# STM32F103T8.net
KiCad netlist of a schematic drawn in Altium Designer
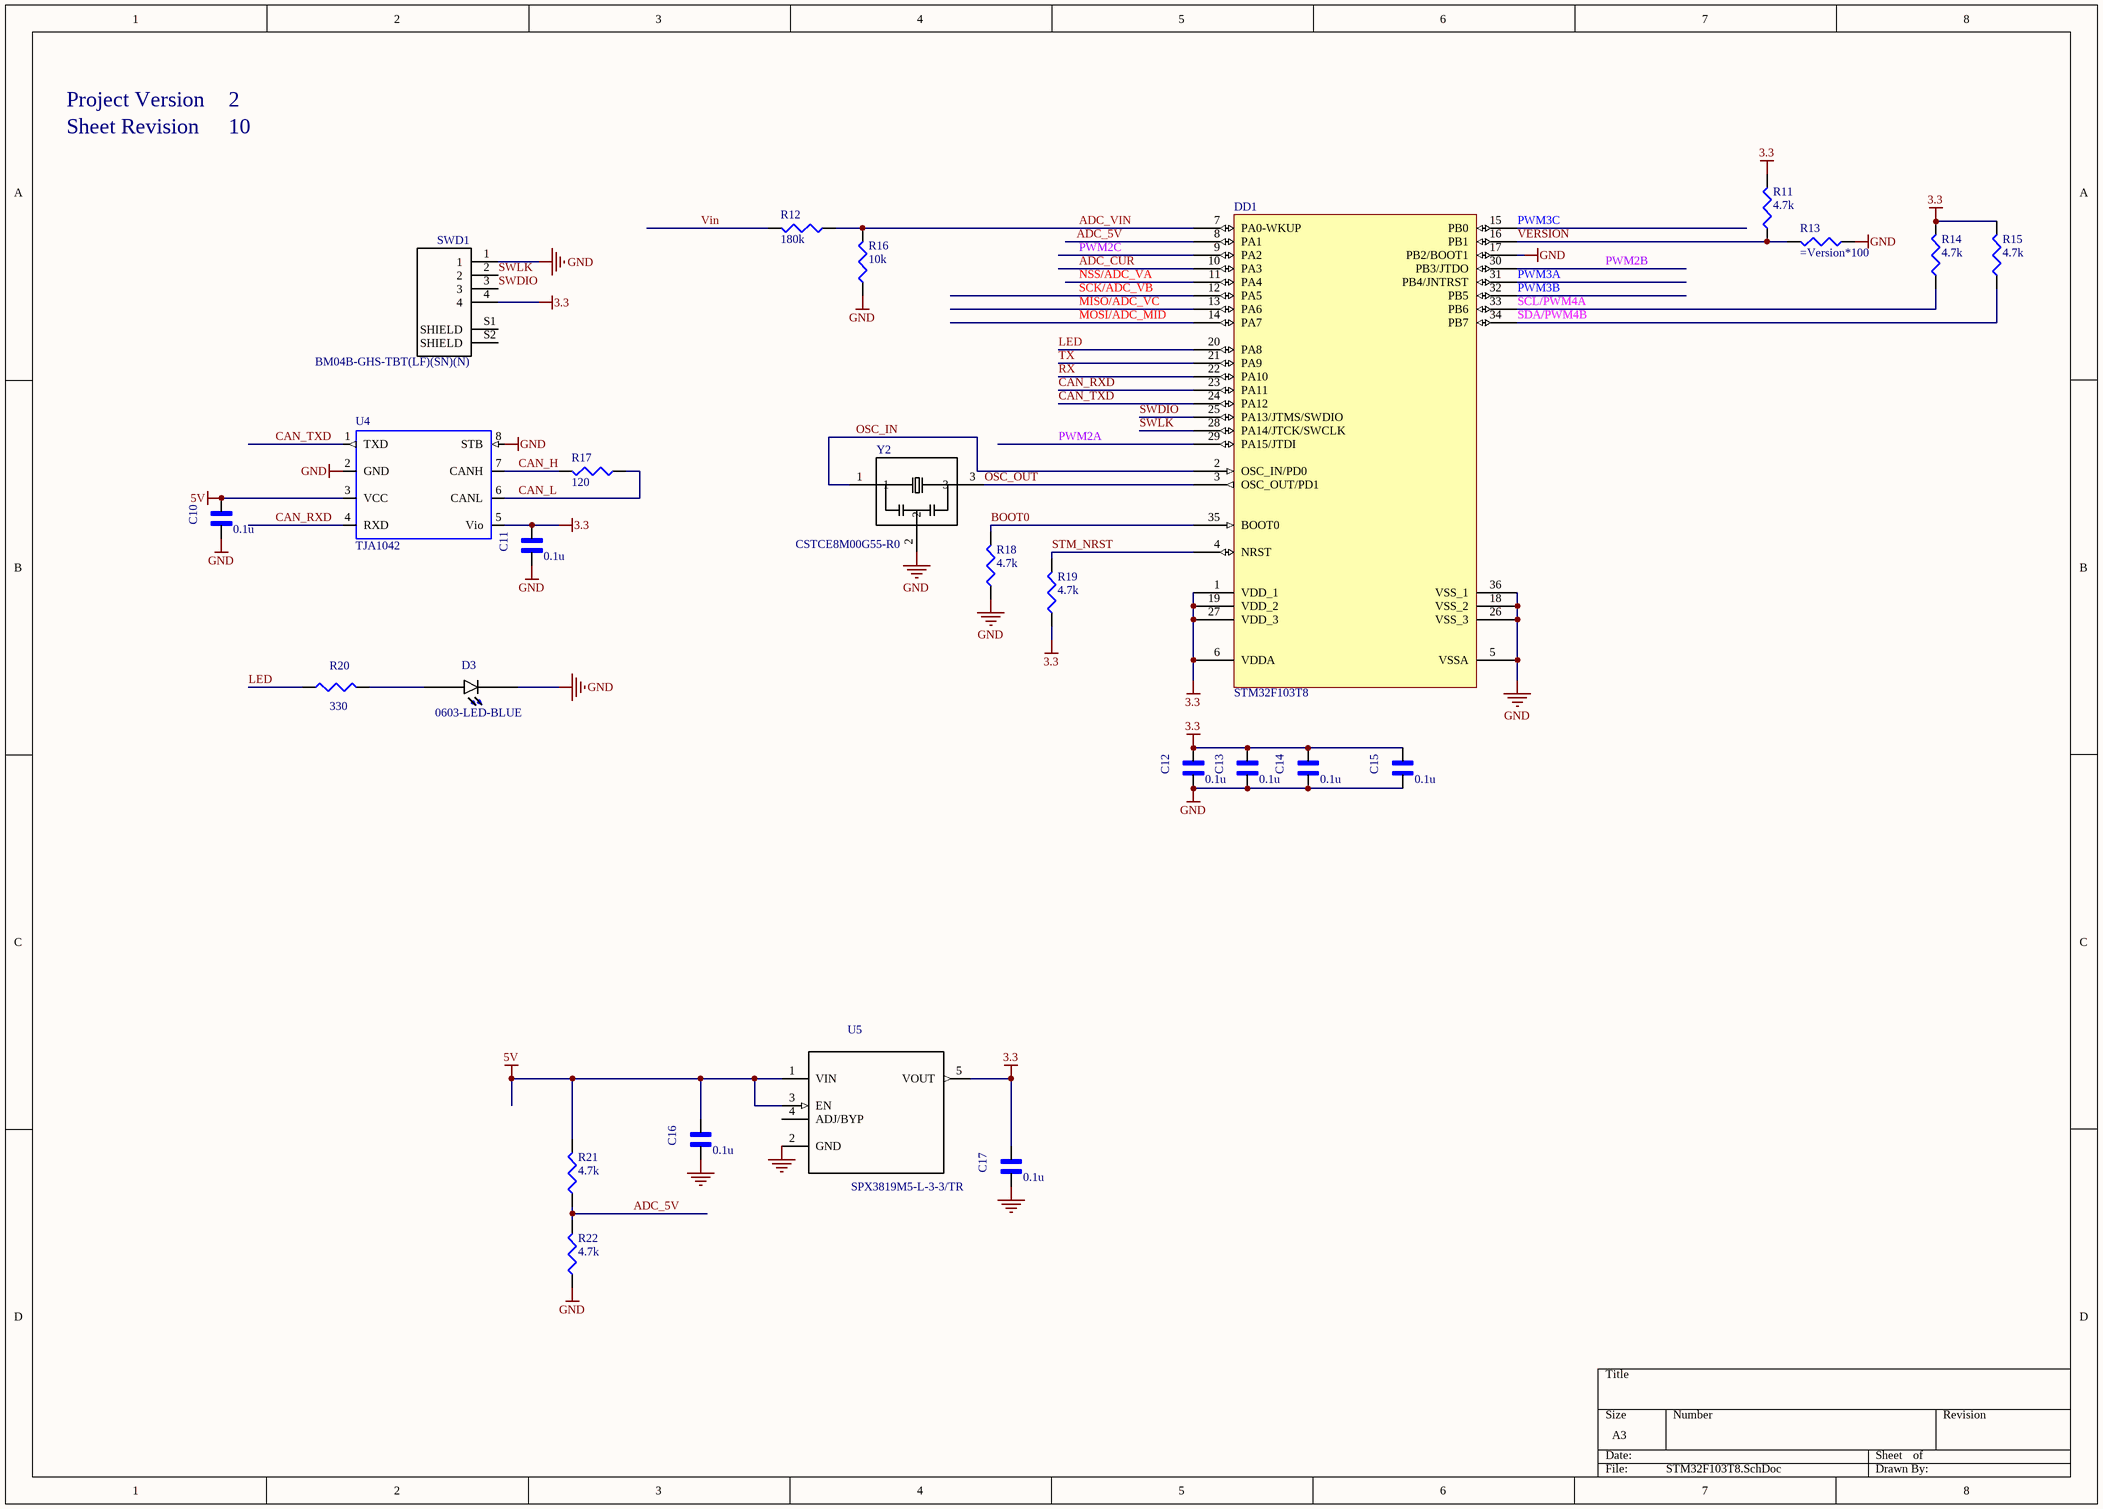
[diagram p0: STM32F103T8.SchDoc]

(export (version "E")
  (design (tool "Eeschema 10.0.6"))
  (components
    (comp (ref "C10")
      (value "0.1u")
      (footprint "*CAPC1608X90")
      (description "Cap Thin Film 0.1uf 50v 0603")
      (fields (field (name "MF") "AVX") (field (name "MP") "GX035C104MAT2-500"))
      (libsource (lib "lib") (part "GX035C104MAT2-500"))
    )
    (comp (ref "C11")
      (value "0.1u")
      (footprint "*CAPC1608X90")
      (description "Cap Thin Film 0.1uf 50v 0603")
      (fields (field (name "MF") "AVX") (field (name "MP") "GX035C104MAT2-500"))
      (libsource (lib "lib") (part "GX035C104MAT2-500"))
    )
    (comp (ref "C12")
      (value "0.1u")
      (footprint "*CAPC1608X90")
      (description "Cap Thin Film 0.1uf 50v 0603")
      (fields (field (name "MF") "AVX") (field (name "MP") "GX035C104MAT2-500"))
      (libsource (lib "lib") (part "GX035C104MAT2-500"))
    )
    (comp (ref "C13")
      (value "0.1u")
      (footprint "*CAPC1608X90")
      (description "Cap Thin Film 0.1uf 50v 0603")
      (fields (field (name "MF") "AVX") (field (name "MP") "GX035C104MAT2-500"))
      (libsource (lib "lib") (part "GX035C104MAT2-500"))
    )
    (comp (ref "C14")
      (value "0.1u")
      (footprint "*CAPC1608X90")
      (description "Cap Thin Film 0.1uf 50v 0603")
      (fields (field (name "MF") "AVX") (field (name "MP") "GX035C104MAT2-500"))
      (libsource (lib "lib") (part "GX035C104MAT2-500"))
    )
    (comp (ref "C15")
      (value "0.1u")
      (footprint "*CAPC1608X90")
      (description "Cap Thin Film 0.1uf 50v 0603")
      (fields (field (name "MF") "AVX") (field (name "MP") "GX035C104MAT2-500"))
      (libsource (lib "lib") (part "GX035C104MAT2-500"))
    )
    (comp (ref "C16")
      (value "0.1u")
      (footprint "*CAPC1608X90")
      (description "Cap Thin Film 0.1uf 50v 0603")
      (fields (field (name "MF") "AVX") (field (name "MP") "GX035C104MAT2-500"))
      (libsource (lib "lib") (part "GX035C104MAT2-500"))
    )
    (comp (ref "C17")
      (value "0.1u")
      (footprint "*CAPC1608X90")
      (description "Cap Thin Film 0.1uf 50v 0603")
      (fields (field (name "MF") "AVX") (field (name "MP") "GX035C104MAT2-500"))
      (libsource (lib "lib") (part "GX035C104MAT2-500"))
    )
    (comp (ref "D3")
      (value "0603-LED-BLUE")
      (footprint "*LEDM1608X80_LTE-C1906R-14(Primary)")
      (description "LED IrLED Chip LED 2-Pin SMD T/R")
      (libsource (lib "lib") (part "LTE-C1906R-14"))
    )
    (comp (ref "DD1")
      (value "STM32F103T8")
      (footprint "*QFN50P600X600X100-37N")
      (description "STM32F103T8U6, Микроконтроллер 32BIT ARM 64K FLASH [VFQFPN-36]")
      (fields (field (name "MF") "STM") (field (name "MP") "STM32F103T8U6"))
      (libsource (lib "lib") (part "STM32F103T8"))
    )
    (comp (ref "R11")
      (value "4.7k")
      (footprint "J1-0603")
      (description "Resistor")
      (fields (field (name "MP") "4.7K 1% 0603") (field (name "Comment") "Res3"))
      (libsource (lib "Miscellaneous Devices") (part "Res3"))
    )
    (comp (ref "R12")
      (value "180k")
      (footprint "J1-0603")
      (description "Resistor")
      (fields (field (name "MP") "180K 1% 0603") (field (name "Comment") "Res3"))
      (libsource (lib "Miscellaneous Devices") (part "Res3"))
    )
    (comp (ref "R13")
      (value "Res3")
      (footprint "J1-0603")
      (description "Resistor")
      (fields (field (name "MP") "4.7K 1% 0603"))
      (libsource (lib "Miscellaneous Devices") (part "Res3"))
    )
    (comp (ref "R14")
      (value "4.7k")
      (footprint "J1-0603")
      (description "Resistor")
      (fields (field (name "MP") "4.7K 1% 0603") (field (name "Comment") "Res3"))
      (libsource (lib "Miscellaneous Devices") (part "Res3"))
    )
    (comp (ref "R15")
      (value "4.7k")
      (footprint "J1-0603")
      (description "Resistor")
      (fields (field (name "MP") "4.7K 1% 0603") (field (name "Comment") "Res3"))
      (libsource (lib "Miscellaneous Devices") (part "Res3"))
    )
    (comp (ref "R16")
      (value "10k")
      (footprint "J1-0603")
      (description "Resistor")
      (fields (field (name "MP") "4.7K 1% 0603") (field (name "Comment") "Res3"))
      (libsource (lib "Miscellaneous Devices") (part "Res3"))
    )
    (comp (ref "R17")
      (value "120")
      (footprint "J1-0603")
      (description "120 Ohms 1 0.1 W 1 10 W Chip Resistor 0603 1608 Metric Thick Film")
      (fields (field (name "MP") "RC0603FR-07120RL") (field (name "Comment") "Res3"))
      (libsource (lib "Miscellaneous Devices") (part "Res3"))
    )
    (comp (ref "R18")
      (value "4.7k")
      (footprint "J1-0603")
      (description "Resistor")
      (fields (field (name "MP") "4.7K 1% 0603") (field (name "Comment") "Res3"))
      (libsource (lib "Miscellaneous Devices") (part "Res3"))
    )
    (comp (ref "R19")
      (value "4.7k")
      (footprint "J1-0603")
      (description "Resistor")
      (fields (field (name "MP") "4.7K 1% 0603") (field (name "Comment") "Res3"))
      (libsource (lib "Miscellaneous Devices") (part "Res3"))
    )
    (comp (ref "R20")
      (value "330")
      (footprint "J1-0603")
      (description "Resistor")
      (fields (field (name "MP") "RC0603FR-07330RL") (field (name "Comment") "Res3"))
      (libsource (lib "Miscellaneous Devices") (part "Res3"))
    )
    (comp (ref "R21")
      (value "4.7k")
      (footprint "J1-0603")
      (description "Resistor")
      (fields (field (name "MP") "4.7K 1% 0603") (field (name "Comment") "Res3"))
      (libsource (lib "Miscellaneous Devices") (part "Res3"))
    )
    (comp (ref "R22")
      (value "4.7k")
      (footprint "J1-0603")
      (description "Resistor")
      (fields (field (name "MP") "4.7K 1% 0603") (field (name "Comment") "Res3"))
      (libsource (lib "Miscellaneous Devices") (part "Res3"))
    )
    (comp (ref "SWD1")
      (value "BM04B-GHS-TBT(LF)(SN)(N)")
      (footprint "JST_BM04B-GHS-holes")
      (description "Conn Shrouded Header HDR 4 POS 1.25mm Solder ST SMD Reel")
      (fields (field (name "MF") "JST Sales") (field (name "MP") "SM04B-GHS-TB(LF)(SN)"))
      (libsource (lib "lib") (part "BM04B-GHS-TBT(LF)(SN)(N)"))
    )
    (comp (ref "U4")
      (value "TJA1042")
      (footprint "SOT782-1")
      (description "1/1 Transceiver Half CANbus 8-SO")
      (fields (field (name "MF") "NXP USA"))
      (libsource (lib "lib") (part "TJA1042"))
    )
    (comp (ref "U5")
      (value "SPX3819M5-L-3-3/TR")
      (footprint "*SOT95P280X145-5N")
      (description "Low Dropout Voltage Regulator, Adjustable 0.5A, В±1%, 2.5 to 16 Vin, 5-Pin SOT-23")
      (fields (field (name "MF") "MaxLinear, Inc."))
      (libsource (lib "DC_DC") (part "SPX3819M5-L"))
    )
    (comp (ref "Y2")
      (value "CSTCE8M00G55-R0")
      (footprint "*OSC_CSTCE8M00G55-R0")
      (description "Ceramic Resonator 8MHz ??0.5% _Tol_ ??0.2% _Stability_ 33pF 40Ohm 3-Pin CSMD T/R")
      (fields (field (name "MF") "Murata"))
      (libsource (lib "DC_DC") (part "CSTCE8M00G55-R0"))
    )
  )
  (nets
    (net (code "1") (name "/ADC_5V") (class "Default")
      (node (ref "DD1") (pin "8") (pinfunction "PA1_8") (pintype "bidirectional"))
      (node (ref "R21") (pin "1") (pinfunction "1_1") (pintype "passive"))
      (node (ref "R22") (pin "2") (pinfunction "2_2") (pintype "passive"))
    )
    (net (code "2") (name "/ADC_CUR") (class "Default")
      (node (ref "DD1") (pin "10") (pinfunction "PA3_10") (pintype "bidirectional"))
    )
    (net (code "3") (name "/ADC_VIN") (class "Default")
      (node (ref "DD1") (pin "7") (pinfunction "PA0-WKUP_7") (pintype "bidirectional"))
      (node (ref "R12") (pin "1") (pinfunction "1_1") (pintype "passive"))
      (node (ref "R16") (pin "2") (pinfunction "2_2") (pintype "passive"))
    )
    (net (code "4") (name "/BOOT0") (class "Default")
      (node (ref "DD1") (pin "35") (pinfunction "BOOT0_35") (pintype "input"))
      (node (ref "R18") (pin "2") (pinfunction "2_2") (pintype "passive"))
    )
    (net (code "5") (name "/CAN_H") (class "Default")
      (node (ref "R17") (pin "2") (pinfunction "2_2") (pintype "passive"))
      (node (ref "U4") (pin "7") (pinfunction "CANH_7") (pintype "bidirectional"))
    )
    (net (code "6") (name "/CAN_L") (class "Default")
      (node (ref "R17") (pin "1") (pinfunction "1_1") (pintype "passive"))
      (node (ref "U4") (pin "6") (pinfunction "CANL_6") (pintype "bidirectional"))
    )
    (net (code "7") (name "/CAN_RXD") (class "Default")
      (node (ref "DD1") (pin "23") (pinfunction "PA11_23") (pintype "bidirectional"))
      (node (ref "U4") (pin "4") (pinfunction "RXD_4") (pintype "bidirectional"))
    )
    (net (code "8") (name "/CAN_TXD") (class "Default")
      (node (ref "DD1") (pin "24") (pinfunction "PA12_24") (pintype "bidirectional"))
      (node (ref "U4") (pin "1") (pinfunction "TXD_1") (pintype "output"))
    )
    (net (code "9") (name "/LED") (class "Default")
      (node (ref "DD1") (pin "20") (pinfunction "PA8_20") (pintype "bidirectional"))
      (node (ref "R20") (pin "1") (pinfunction "1_1") (pintype "passive"))
    )
    (net (code "10") (name "/MISO{slash}ADC_VC") (class "Default")
      (node (ref "DD1") (pin "13") (pinfunction "PA6_13") (pintype "bidirectional"))
    )
    (net (code "11") (name "/MOSI{slash}ADC_MID") (class "Default")
      (node (ref "DD1") (pin "14") (pinfunction "PA7_14") (pintype "bidirectional"))
    )
    (net (code "12") (name "/NSS{slash}ADC_VA") (class "Default")
      (node (ref "DD1") (pin "11") (pinfunction "PA4_11") (pintype "bidirectional"))
    )
    (net (code "13") (name "/OSC_IN") (class "Default")
      (node (ref "DD1") (pin "2") (pinfunction "OSC_IN/PD0_2") (pintype "input"))
      (node (ref "Y2") (pin "1") (pinfunction "1_1") (pintype "passive"))
    )
    (net (code "14") (name "/OSC_OUT") (class "Default")
      (node (ref "DD1") (pin "3") (pinfunction "OSC_OUT/PD1_3") (pintype "output"))
      (node (ref "Y2") (pin "3") (pinfunction "3_3") (pintype "passive"))
    )
    (net (code "15") (name "/PWM2A") (class "Default")
      (node (ref "DD1") (pin "29") (pinfunction "PA15/JTDI_29") (pintype "bidirectional"))
    )
    (net (code "16") (name "/PWM2B") (class "Default")
      (node (ref "DD1") (pin "30") (pinfunction "PB3/JTDO_30") (pintype "bidirectional"))
    )
    (net (code "17") (name "/PWM2C") (class "Default")
      (node (ref "DD1") (pin "9") (pinfunction "PA2_9") (pintype "bidirectional"))
    )
    (net (code "18") (name "/PWM3A") (class "Default")
      (node (ref "DD1") (pin "31") (pinfunction "PB4/JNTRST_31") (pintype "bidirectional"))
    )
    (net (code "19") (name "/PWM3B") (class "Default")
      (node (ref "DD1") (pin "32") (pinfunction "PB5_32") (pintype "bidirectional"))
    )
    (net (code "20") (name "/PWM3C") (class "Default")
      (node (ref "DD1") (pin "15") (pinfunction "PB0_15") (pintype "bidirectional"))
    )
    (net (code "21") (name "/RX") (class "Default")
      (node (ref "DD1") (pin "22") (pinfunction "PA10_22") (pintype "bidirectional"))
    )
    (net (code "22") (name "/SCK{slash}ADC_VB") (class "Default")
      (node (ref "DD1") (pin "12") (pinfunction "PA5_12") (pintype "bidirectional"))
    )
    (net (code "23") (name "/SCL{slash}PWM4A") (class "Default")
      (node (ref "DD1") (pin "33") (pinfunction "PB6_33") (pintype "bidirectional"))
      (node (ref "R14") (pin "1") (pinfunction "1_1") (pintype "passive"))
    )
    (net (code "24") (name "/SDA{slash}PWM4B") (class "Default")
      (node (ref "DD1") (pin "34") (pinfunction "PB7_34") (pintype "bidirectional"))
      (node (ref "R15") (pin "1") (pinfunction "1_1") (pintype "passive"))
    )
    (net (code "25") (name "/STM_NRST") (class "Default")
      (node (ref "DD1") (pin "4") (pinfunction "NRST_4") (pintype "bidirectional"))
      (node (ref "R19") (pin "2") (pinfunction "2_2") (pintype "passive"))
    )
    (net (code "26") (name "/SWDIO") (class "Default")
      (node (ref "DD1") (pin "25") (pinfunction "PA13/JTMS/SWDIO_25") (pintype "bidirectional"))
      (node (ref "SWD1") (pin "3") (pinfunction "3_3") (pintype "passive"))
    )
    (net (code "27") (name "/SWLK") (class "Default")
      (node (ref "DD1") (pin "28") (pinfunction "PA14/JTCK/SWCLK_28") (pintype "bidirectional"))
      (node (ref "SWD1") (pin "2") (pinfunction "2_2") (pintype "passive"))
    )
    (net (code "28") (name "/TX") (class "Default")
      (node (ref "DD1") (pin "21") (pinfunction "PA9_21") (pintype "bidirectional"))
    )
    (net (code "29") (name "/VERSION") (class "Default")
      (node (ref "DD1") (pin "16") (pinfunction "PB1_16") (pintype "bidirectional"))
      (node (ref "R11") (pin "1") (pinfunction "1_1") (pintype "passive"))
      (node (ref "R13") (pin "2") (pinfunction "2_2") (pintype "passive"))
    )
    (net (code "30") (name "/Vin") (class "Default")
      (node (ref "R12") (pin "2") (pinfunction "2_2") (pintype "passive"))
    )
    (net (code "31") (name "3.3") (class "Default")
      (node (ref "C11") (pin "1") (pinfunction "1_1") (pintype "passive"))
      (node (ref "C12") (pin "1") (pinfunction "1_1") (pintype "passive"))
      (node (ref "C13") (pin "1") (pinfunction "1_1") (pintype "passive"))
      (node (ref "C14") (pin "1") (pinfunction "1_1") (pintype "passive"))
      (node (ref "C15") (pin "1") (pinfunction "1_1") (pintype "passive"))
      (node (ref "C17") (pin "1") (pinfunction "1_1") (pintype "passive"))
      (node (ref "DD1") (pin "1") (pinfunction "VDD_1_1") (pintype "power_in"))
      (node (ref "DD1") (pin "19") (pinfunction "VDD_2_19") (pintype "power_in"))
      (node (ref "DD1") (pin "27") (pinfunction "VDD_3_27") (pintype "power_in"))
      (node (ref "DD1") (pin "6") (pinfunction "VDDA_6") (pintype "power_in"))
      (node (ref "R11") (pin "2") (pinfunction "2_2") (pintype "passive"))
      (node (ref "R14") (pin "2") (pinfunction "2_2") (pintype "passive"))
      (node (ref "R15") (pin "2") (pinfunction "2_2") (pintype "passive"))
      (node (ref "R19") (pin "1") (pinfunction "1_1") (pintype "passive"))
      (node (ref "SWD1") (pin "4") (pinfunction "4_4") (pintype "passive"))
      (node (ref "U4") (pin "5") (pinfunction "Vio_5") (pintype "power_in"))
      (node (ref "U5") (pin "5") (pinfunction "VOUT_5") (pintype "output"))
    )
    (net (code "32") (name "5V") (class "Default")
      (node (ref "C10") (pin "1") (pinfunction "1_1") (pintype "passive"))
      (node (ref "C16") (pin "1") (pinfunction "1_1") (pintype "passive"))
      (node (ref "R21") (pin "2") (pinfunction "2_2") (pintype "passive"))
      (node (ref "U4") (pin "3") (pinfunction "VCC_3") (pintype "power_in"))
      (node (ref "U5") (pin "1") (pinfunction "VIN_1") (pintype "power_in"))
      (node (ref "U5") (pin "3") (pinfunction "EN_3") (pintype "input"))
    )
    (net (code "33") (name "GND") (class "Default")
      (node (ref "C10") (pin "2") (pinfunction "2_2") (pintype "passive"))
      (node (ref "C11") (pin "2") (pinfunction "2_2") (pintype "passive"))
      (node (ref "C12") (pin "2") (pinfunction "2_2") (pintype "passive"))
      (node (ref "C13") (pin "2") (pinfunction "2_2") (pintype "passive"))
      (node (ref "C14") (pin "2") (pinfunction "2_2") (pintype "passive"))
      (node (ref "C15") (pin "2") (pinfunction "2_2") (pintype "passive"))
      (node (ref "C16") (pin "2") (pinfunction "2_2") (pintype "passive"))
      (node (ref "C17") (pin "2") (pinfunction "2_2") (pintype "passive"))
      (node (ref "D3") (pin "C") (pinfunction "C_C") (pintype "passive"))
      (node (ref "DD1") (pin "17") (pinfunction "PB2/BOOT1_17") (pintype "bidirectional"))
      (node (ref "DD1") (pin "18") (pinfunction "VSS_2_18") (pintype "power_in"))
      (node (ref "DD1") (pin "26") (pinfunction "VSS_3_26") (pintype "power_in"))
      (node (ref "DD1") (pin "36") (pinfunction "VSS_1_36") (pintype "power_in"))
      (node (ref "DD1") (pin "5") (pinfunction "VSSA_5") (pintype "power_in"))
      (node (ref "R13") (pin "1") (pinfunction "1_1") (pintype "passive"))
      (node (ref "R16") (pin "1") (pinfunction "1_1") (pintype "passive"))
      (node (ref "R18") (pin "1") (pinfunction "1_1") (pintype "passive"))
      (node (ref "R22") (pin "1") (pinfunction "1_1") (pintype "passive"))
      (node (ref "SWD1") (pin "1") (pinfunction "1_1") (pintype "passive"))
      (node (ref "U4") (pin "2") (pinfunction "GND_2") (pintype "power_in"))
      (node (ref "U4") (pin "8") (pinfunction "STB_8") (pintype "input"))
      (node (ref "U5") (pin "2") (pinfunction "GND_2") (pintype "passive"))
      (node (ref "Y2") (pin "2") (pinfunction "2_2") (pintype "power_in"))
    )
    (net (code "34") (name "Net-(D3-PadA)") (class "Default")
      (node (ref "D3") (pin "A") (pinfunction "A_A") (pintype "passive"))
      (node (ref "R20") (pin "2") (pinfunction "2_2") (pintype "passive"))
    )
    (net (code "35") (name "unconnected-(SWD1-SHIELD-PadS1)") (class "Default")
      (node (ref "SWD1") (pin "S1") (pinfunction "SHIELD_S1") (pintype "passive"))
    )
    (net (code "36") (name "unconnected-(SWD1-SHIELD-PadS2)") (class "Default")
      (node (ref "SWD1") (pin "S2") (pinfunction "SHIELD_S2") (pintype "passive"))
    )
    (net (code "37") (name "unconnected-(U5-ADJ{slash}BYP-Pad4)") (class "Default")
      (node (ref "U5") (pin "4") (pinfunction "ADJ/BYP_4") (pintype "passive"))
    )
  )
)
